# RoboFly.net
KiCad netlist of a schematic drawn in Altium Designer
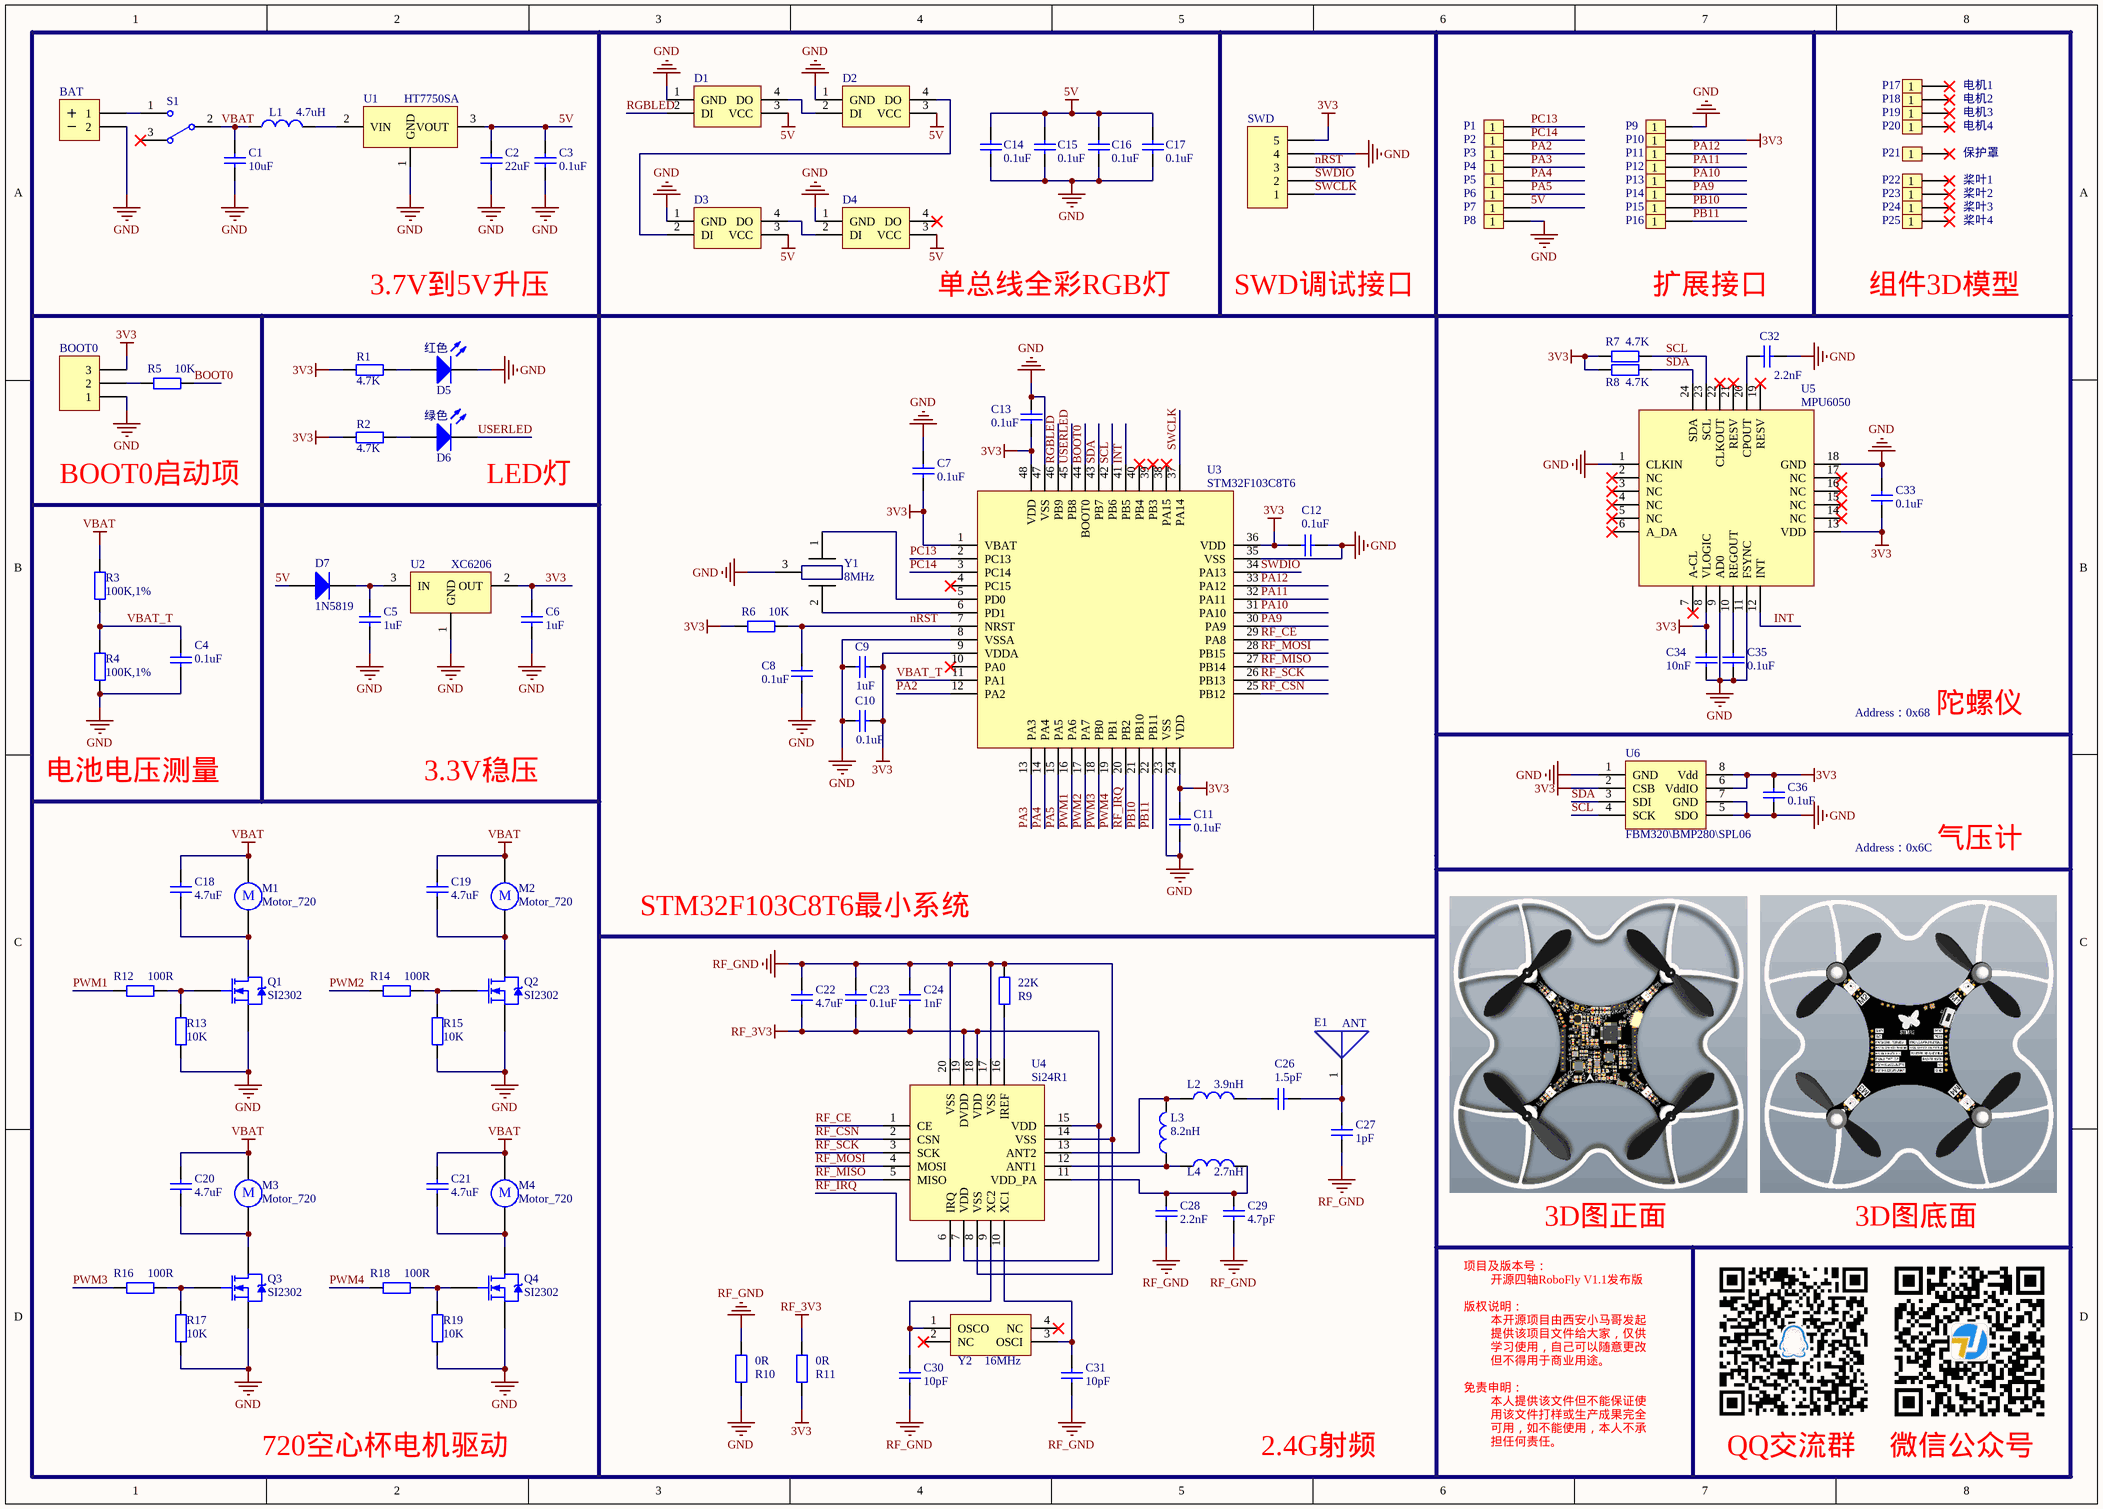
[diagram p0: RoboFly.SchDoc]

(export (version "E")
  (design (tool "Eeschema 10.0.6"))
  (components
    (comp (ref "BAT")
      (value "BAT")
      (footprint "BAT")
      (description "Header, 2-Pin")
      (fields (field (name "PUBLISHER") "mazhongwei"))
      (libsource (lib "RoboFly") (part "BAT"))
    )
    (comp (ref "BOOT0")
      (value "BOOT")
      (footprint "HEADER1X3")
      (description "Header, 3-Pin")
      (fields (field (name "PUBLISHER") "Altium Limited"))
      (libsource (lib "RoboFly") (part "Header 3"))
    )
    (comp (ref "C1")
      (value "10uF")
      (footprint "C_0603")
      (fields (field (name "Comment") "C_0603") (field (name "PUBLISHER") "Altium Limited"))
      (libsource (lib "RoboFly") (part "C_0603"))
    )
    (comp (ref "C2")
      (value "22uF")
      (footprint "C_0603")
      (fields (field (name "Comment") "C_0603") (field (name "PUBLISHER") "Altium Limited"))
      (libsource (lib "RoboFly") (part "C_0603"))
    )
    (comp (ref "C3")
      (value "0.1uF")
      (footprint "C_0603")
      (fields (field (name "Comment") "C_0603") (field (name "PUBLISHER") "Altium Limited"))
      (libsource (lib "RoboFly") (part "C_0603"))
    )
    (comp (ref "C4")
      (value "0.1uF")
      (footprint "C_0603")
      (fields (field (name "Comment") "C_0603") (field (name "PUBLISHER") "Altium Limited"))
      (libsource (lib "RoboFly") (part "C_0603"))
    )
    (comp (ref "C5")
      (value "1uF")
      (footprint "C_0603")
      (fields (field (name "Comment") "C_0603") (field (name "PUBLISHER") "Altium Limited"))
      (libsource (lib "RoboFly") (part "C_0603"))
    )
    (comp (ref "C6")
      (value "1uF")
      (footprint "C_0603")
      (fields (field (name "Comment") "C_0603") (field (name "PUBLISHER") "Altium Limited"))
      (libsource (lib "RoboFly") (part "C_0603"))
    )
    (comp (ref "C7")
      (value "0.1uF")
      (footprint "C_0603")
      (fields (field (name "Comment") "C_0603") (field (name "PUBLISHER") "Altium Limited"))
      (libsource (lib "RoboFly") (part "C_0603"))
    )
    (comp (ref "C8")
      (value "0.1uF")
      (footprint "C_0603")
      (fields (field (name "Comment") "C_0603") (field (name "PUBLISHER") "Altium Limited"))
      (libsource (lib "RoboFly") (part "C_0603"))
    )
    (comp (ref "C9")
      (value "1uF")
      (footprint "C_0603")
      (fields (field (name "Comment") "C_0603") (field (name "PUBLISHER") "Altium Limited"))
      (libsource (lib "RoboFly") (part "C_0603"))
    )
    (comp (ref "C10")
      (value "0.1uF")
      (footprint "C_0603")
      (fields (field (name "Comment") "C_0603") (field (name "PUBLISHER") "Altium Limited"))
      (libsource (lib "RoboFly") (part "C_0603"))
    )
    (comp (ref "C11")
      (value "0.1uF")
      (footprint "C_0603")
      (fields (field (name "Comment") "C_0603") (field (name "PUBLISHER") "Altium Limited"))
      (libsource (lib "RoboFly") (part "C_0603"))
    )
    (comp (ref "C12")
      (value "0.1uF")
      (footprint "C_0603")
      (fields (field (name "Comment") "C_0603") (field (name "PUBLISHER") "Altium Limited"))
      (libsource (lib "RoboFly") (part "C_0603"))
    )
    (comp (ref "C13")
      (value "0.1uF")
      (footprint "C_0603")
      (fields (field (name "Comment") "C_0603") (field (name "PUBLISHER") "Altium Limited"))
      (libsource (lib "RoboFly") (part "C_0603"))
    )
    (comp (ref "C14")
      (value "0.1uF")
      (footprint "C_0603")
      (fields (field (name "Comment") "C_0603") (field (name "PUBLISHER") "Altium Limited"))
      (libsource (lib "RoboFly") (part "C_0603"))
    )
    (comp (ref "C15")
      (value "0.1uF")
      (footprint "C_0603")
      (fields (field (name "Comment") "C_0603") (field (name "PUBLISHER") "Altium Limited"))
      (libsource (lib "RoboFly") (part "C_0603"))
    )
    (comp (ref "C16")
      (value "0.1uF")
      (footprint "C_0603")
      (fields (field (name "Comment") "C_0603") (field (name "PUBLISHER") "Altium Limited"))
      (libsource (lib "RoboFly") (part "C_0603"))
    )
    (comp (ref "C17")
      (value "0.1uF")
      (footprint "C_0603")
      (fields (field (name "Comment") "C_0603") (field (name "PUBLISHER") "Altium Limited"))
      (libsource (lib "RoboFly") (part "C_0603"))
    )
    (comp (ref "C18")
      (value "4.7uF")
      (footprint "C_0603")
      (fields (field (name "Comment") "C_0603") (field (name "PUBLISHER") "Altium Limited"))
      (libsource (lib "RoboFly") (part "C_0603"))
    )
    (comp (ref "C19")
      (value "4.7uF")
      (footprint "C_0603")
      (fields (field (name "Comment") "C_0603") (field (name "PUBLISHER") "Altium Limited"))
      (libsource (lib "RoboFly") (part "C_0603"))
    )
    (comp (ref "C20")
      (value "4.7uF")
      (footprint "C_0603")
      (fields (field (name "Comment") "C_0603") (field (name "PUBLISHER") "Altium Limited"))
      (libsource (lib "RoboFly") (part "C_0603"))
    )
    (comp (ref "C21")
      (value "4.7uF")
      (footprint "C_0603")
      (fields (field (name "Comment") "C_0603") (field (name "PUBLISHER") "Altium Limited"))
      (libsource (lib "RoboFly") (part "C_0603"))
    )
    (comp (ref "C22")
      (value "4.7uF")
      (footprint "C_0603")
      (fields (field (name "Comment") "C_0603") (field (name "PUBLISHER") "Altium Limited"))
      (libsource (lib "RoboFly") (part "C_0603"))
    )
    (comp (ref "C23")
      (value "0.1uF")
      (footprint "C_0603")
      (fields (field (name "Comment") "C_0603") (field (name "PUBLISHER") "Altium Limited"))
      (libsource (lib "RoboFly") (part "C_0603"))
    )
    (comp (ref "C24")
      (value "1nF")
      (footprint "C_0603")
      (fields (field (name "Comment") "C_0603") (field (name "PUBLISHER") "Altium Limited"))
      (libsource (lib "RoboFly") (part "C_0603"))
    )
    (comp (ref "C26")
      (value "1.5pF")
      (footprint "C_0603")
      (fields (field (name "Comment") "C_0603") (field (name "PUBLISHER") "Altium Limited"))
      (libsource (lib "RoboFly") (part "C_0603"))
    )
    (comp (ref "C27")
      (value "1pF")
      (footprint "C_0603")
      (fields (field (name "Comment") "C_0603") (field (name "PUBLISHER") "Altium Limited"))
      (libsource (lib "RoboFly") (part "C_0603"))
    )
    (comp (ref "C28")
      (value "2.2nF")
      (footprint "C_0603")
      (fields (field (name "Comment") "C_0603") (field (name "PUBLISHER") "Altium Limited"))
      (libsource (lib "RoboFly") (part "C_0603"))
    )
    (comp (ref "C29")
      (value "4.7pF")
      (footprint "C_0603")
      (fields (field (name "Comment") "C_0603") (field (name "PUBLISHER") "Altium Limited"))
      (libsource (lib "RoboFly") (part "C_0603"))
    )
    (comp (ref "C30")
      (value "10pF")
      (footprint "C_0603")
      (fields (field (name "Comment") "C_0603") (field (name "PUBLISHER") "Altium Limited"))
      (libsource (lib "RoboFly") (part "C_0603"))
    )
    (comp (ref "C31")
      (value "10pF")
      (footprint "C_0603")
      (fields (field (name "Comment") "C_0603") (field (name "PUBLISHER") "Altium Limited"))
      (libsource (lib "RoboFly") (part "C_0603"))
    )
    (comp (ref "C32")
      (value "2.2nF")
      (footprint "C_0603")
      (fields (field (name "Comment") "C_0603") (field (name "PUBLISHER") "Altium Limited"))
      (libsource (lib "RoboFly") (part "C_0603"))
    )
    (comp (ref "C33")
      (value "0.1uF")
      (footprint "C_0603")
      (fields (field (name "Comment") "C_0603") (field (name "PUBLISHER") "Altium Limited"))
      (libsource (lib "RoboFly") (part "C_0603"))
    )
    (comp (ref "C34")
      (value "10nF")
      (footprint "C_0603")
      (fields (field (name "Comment") "C_0603") (field (name "PUBLISHER") "Altium Limited"))
      (libsource (lib "RoboFly") (part "C_0603"))
    )
    (comp (ref "C35")
      (value "0.1uF")
      (footprint "C_0603")
      (fields (field (name "Comment") "C_0603") (field (name "PUBLISHER") "Altium Limited"))
      (libsource (lib "RoboFly") (part "C_0603"))
    )
    (comp (ref "C36")
      (value "0.1uF")
      (footprint "C_0603")
      (fields (field (name "Comment") "C_0603") (field (name "PUBLISHER") "Altium Limited"))
      (libsource (lib "RoboFly") (part "C_0603"))
    )
    (comp (ref "D1")
      (value "P923D")
      (footprint "RGB_LED_5050")
      (fields (field (name "PUBLISHER") "mazhongwei"))
      (libsource (lib "RoboFly") (part "P923D"))
    )
    (comp (ref "D2")
      (value "P923D")
      (footprint "RGB_LED_5050")
      (fields (field (name "PUBLISHER") "mazhongwei"))
      (libsource (lib "RoboFly") (part "P923D"))
    )
    (comp (ref "D3")
      (value "P923D")
      (footprint "RGB_LED_5050")
      (fields (field (name "PUBLISHER") "mazhongwei"))
      (libsource (lib "RoboFly") (part "P923D"))
    )
    (comp (ref "D4")
      (value "P923D")
      (footprint "RGB_LED_5050")
      (fields (field (name "PUBLISHER") "mazhongwei"))
      (libsource (lib "RoboFly") (part "P923D"))
    )
    (comp (ref "D5")
      (value "红色")
      (footprint "LED-0603")
      (description "发光二极管")
      (fields (field (name "PUBLISHER") "Altium Limited"))
      (libsource (lib "RoboFly") (part "LED 0603"))
    )
    (comp (ref "D6")
      (value "绿色")
      (footprint "LED-0603")
      (description "发光二极管")
      (fields (field (name "PUBLISHER") "Altium Limited"))
      (libsource (lib "RoboFly") (part "LED 0603"))
    )
    (comp (ref "D7")
      (value "1N5819")
      (footprint "SOD-123")
      (description "Default Diode")
      (fields (field (name "PUBLISHER") "mazhongwei"))
      (libsource (lib "RoboFly") (part "Diode"))
    )
    (comp (ref "E1")
      (value "ANT")
      (footprint "ANT")
      (fields (field (name "PUBLISHER") "mazhongwei"))
      (libsource (lib "RoboFly") (part "ANT"))
    )
    (comp (ref "L1")
      (value "4.7uH")
      (footprint "L_1210")
      (description "电感")
      (fields (field (name "Comment") "Inductor") (field (name "PUBLISHER") "Altium Limited"))
      (libsource (lib "RoboFly") (part "Inductor"))
    )
    (comp (ref "L2")
      (value "3.9nH")
      (footprint "L_0603")
      (description "电感")
      (fields (field (name "Comment") "Inductor") (field (name "PUBLISHER") "Altium Limited"))
      (libsource (lib "RoboFly") (part "Inductor_1"))
    )
    (comp (ref "L3")
      (value "8.2nH")
      (footprint "L_0603")
      (description "电感")
      (fields (field (name "Comment") "Inductor") (field (name "PUBLISHER") "Altium Limited"))
      (libsource (lib "RoboFly") (part "Inductor_1"))
    )
    (comp (ref "L4")
      (value "2.7nH")
      (footprint "L_0603")
      (description "电感")
      (fields (field (name "Comment") "Inductor") (field (name "PUBLISHER") "Altium Limited"))
      (libsource (lib "RoboFly") (part "Inductor_1"))
    )
    (comp (ref "M1")
      (value "Motor_720")
      (footprint "MOTOR")
      (description "Motor, General Kind")
      (fields (field (name "PUBLISHER") "mazhongwei"))
      (libsource (lib "RoboFly") (part "Motor_720"))
    )
    (comp (ref "M2")
      (value "Motor_720")
      (footprint "MOTOR")
      (description "Motor, General Kind")
      (fields (field (name "PUBLISHER") "mazhongwei"))
      (libsource (lib "RoboFly") (part "Motor_720"))
    )
    (comp (ref "M3")
      (value "Motor_720")
      (footprint "MOTOR")
      (description "Motor, General Kind")
      (fields (field (name "PUBLISHER") "mazhongwei"))
      (libsource (lib "RoboFly") (part "Motor_720"))
    )
    (comp (ref "M4")
      (value "Motor_720")
      (footprint "MOTOR")
      (description "Motor, General Kind")
      (fields (field (name "PUBLISHER") "mazhongwei"))
      (libsource (lib "RoboFly") (part "Motor_720"))
    )
    (comp (ref "P1")
      (value "Header 1")
      (footprint "HEADER1")
      (fields (field (name "PUBLISHER") "Altium Limited"))
      (libsource (lib "RoboFly") (part "Header 1"))
    )
    (comp (ref "P2")
      (value "Header 1")
      (footprint "HEADER1")
      (fields (field (name "PUBLISHER") "Altium Limited"))
      (libsource (lib "RoboFly") (part "Header 1"))
    )
    (comp (ref "P3")
      (value "Header 1")
      (footprint "HEADER1")
      (fields (field (name "PUBLISHER") "Altium Limited"))
      (libsource (lib "RoboFly") (part "Header 1"))
    )
    (comp (ref "P4")
      (value "Header 1")
      (footprint "HEADER1")
      (fields (field (name "PUBLISHER") "Altium Limited"))
      (libsource (lib "RoboFly") (part "Header 1"))
    )
    (comp (ref "P5")
      (value "Header 1")
      (footprint "HEADER1")
      (fields (field (name "PUBLISHER") "Altium Limited"))
      (libsource (lib "RoboFly") (part "Header 1"))
    )
    (comp (ref "P6")
      (value "Header 1")
      (footprint "HEADER1")
      (fields (field (name "PUBLISHER") "Altium Limited"))
      (libsource (lib "RoboFly") (part "Header 1"))
    )
    (comp (ref "P7")
      (value "Header 1")
      (footprint "HEADER1")
      (fields (field (name "PUBLISHER") "Altium Limited"))
      (libsource (lib "RoboFly") (part "Header 1"))
    )
    (comp (ref "P8")
      (value "Header 1")
      (footprint "HEADER1")
      (fields (field (name "PUBLISHER") "Altium Limited"))
      (libsource (lib "RoboFly") (part "Header 1"))
    )
    (comp (ref "P9")
      (value "Header 1")
      (footprint "HEADER1")
      (fields (field (name "PUBLISHER") "Altium Limited"))
      (libsource (lib "RoboFly") (part "Header 1"))
    )
    (comp (ref "P10")
      (value "Header 1")
      (footprint "HEADER1")
      (fields (field (name "PUBLISHER") "Altium Limited"))
      (libsource (lib "RoboFly") (part "Header 1"))
    )
    (comp (ref "P11")
      (value "Header 1")
      (footprint "HEADER1")
      (fields (field (name "PUBLISHER") "Altium Limited"))
      (libsource (lib "RoboFly") (part "Header 1"))
    )
    (comp (ref "P12")
      (value "Header 1")
      (footprint "HEADER1")
      (fields (field (name "PUBLISHER") "Altium Limited"))
      (libsource (lib "RoboFly") (part "Header 1"))
    )
    (comp (ref "P13")
      (value "Header 1")
      (footprint "HEADER1")
      (fields (field (name "PUBLISHER") "Altium Limited"))
      (libsource (lib "RoboFly") (part "Header 1"))
    )
    (comp (ref "P14")
      (value "Header 1")
      (footprint "HEADER1")
      (fields (field (name "PUBLISHER") "Altium Limited"))
      (libsource (lib "RoboFly") (part "Header 1"))
    )
    (comp (ref "P15")
      (value "Header 1")
      (footprint "HEADER1")
      (fields (field (name "PUBLISHER") "Altium Limited"))
      (libsource (lib "RoboFly") (part "Header 1"))
    )
    (comp (ref "P16")
      (value "Header 1")
      (footprint "HEADER1")
      (fields (field (name "PUBLISHER") "Altium Limited"))
      (libsource (lib "RoboFly") (part "Header 1"))
    )
    (comp (ref "P17")
      (value "Header 1")
      (footprint "720Motor")
      (fields (field (name "PUBLISHER") "Altium Limited"))
      (libsource (lib "RoboFly") (part "Header 1"))
    )
    (comp (ref "P18")
      (value "Header 1")
      (footprint "720Motor")
      (fields (field (name "PUBLISHER") "Altium Limited"))
      (libsource (lib "RoboFly") (part "Header 1"))
    )
    (comp (ref "P19")
      (value "Header 1")
      (footprint "720Motor")
      (fields (field (name "PUBLISHER") "Altium Limited"))
      (libsource (lib "RoboFly") (part "Header 1"))
    )
    (comp (ref "P20")
      (value "Header 1")
      (footprint "720Motor")
      (fields (field (name "PUBLISHER") "Altium Limited"))
      (libsource (lib "RoboFly") (part "Header 1"))
    )
    (comp (ref "P21")
      (value "Header 1")
      (footprint "PROTECT_COVER")
      (fields (field (name "PUBLISHER") "Altium Limited"))
      (libsource (lib "RoboFly") (part "Header 1"))
    )
    (comp (ref "P22")
      (value "Header 1")
      (footprint "BLADEB")
      (fields (field (name "PUBLISHER") "Altium Limited"))
      (libsource (lib "RoboFly") (part "Header 1"))
    )
    (comp (ref "P23")
      (value "Header 1")
      (footprint "BLADEA")
      (fields (field (name "PUBLISHER") "Altium Limited"))
      (libsource (lib "RoboFly") (part "Header 1"))
    )
    (comp (ref "P24")
      (value "Header 1")
      (footprint "BLADEB")
      (fields (field (name "PUBLISHER") "Altium Limited"))
      (libsource (lib "RoboFly") (part "Header 1"))
    )
    (comp (ref "P25")
      (value "Header 1")
      (footprint "BLADEA")
      (fields (field (name "PUBLISHER") "Altium Limited"))
      (libsource (lib "RoboFly") (part "Header 1"))
    )
    (comp (ref "Q1")
      (value "SI2302")
      (footprint "SOT-23(SOT-23-3)")
      (description "N-Channel Power MOSFET")
      (fields (field (name "PUBLISHER") "mazhongwei"))
      (libsource (lib "RoboFly") (part "SI2302"))
    )
    (comp (ref "Q2")
      (value "SI2302")
      (footprint "SOT-23(SOT-23-3)")
      (description "N-Channel Power MOSFET")
      (fields (field (name "PUBLISHER") "mazhongwei"))
      (libsource (lib "RoboFly") (part "SI2302"))
    )
    (comp (ref "Q3")
      (value "SI2302")
      (footprint "SOT-23(SOT-23-3)")
      (description "N-Channel Power MOSFET")
      (fields (field (name "PUBLISHER") "mazhongwei"))
      (libsource (lib "RoboFly") (part "SI2302"))
    )
    (comp (ref "Q4")
      (value "SI2302")
      (footprint "SOT-23(SOT-23-3)")
      (description "N-Channel Power MOSFET")
      (fields (field (name "PUBLISHER") "mazhongwei"))
      (libsource (lib "RoboFly") (part "SI2302"))
    )
    (comp (ref "R1")
      (value "4.7K")
      (footprint "R_0603")
      (fields (field (name "Comment") "R_0603") (field (name "PUBLISHER") "Altium Limited"))
      (libsource (lib "RoboFly") (part "R_0603"))
    )
    (comp (ref "R2")
      (value "4.7K")
      (footprint "R_0603")
      (fields (field (name "Comment") "R_0603") (field (name "PUBLISHER") "Altium Limited"))
      (libsource (lib "RoboFly") (part "R_0603"))
    )
    (comp (ref "R3")
      (value "100K,1%")
      (footprint "R_0603")
      (fields (field (name "Comment") "R_0603") (field (name "PUBLISHER") "Altium Limited"))
      (libsource (lib "") (part "R_0603_1"))
    )
    (comp (ref "R4")
      (value "100K,1%")
      (footprint "R_0603")
      (fields (field (name "Comment") "R_0603") (field (name "PUBLISHER") "Altium Limited"))
      (libsource (lib "") (part "R_0603_1"))
    )
    (comp (ref "R5")
      (value "10K")
      (footprint "R_0603")
      (fields (field (name "Comment") "R_0603") (field (name "PUBLISHER") "Altium Limited"))
      (libsource (lib "RoboFly") (part "R_0603"))
    )
    (comp (ref "R6")
      (value "10K")
      (footprint "R_0603")
      (fields (field (name "Comment") "R_0603") (field (name "PUBLISHER") "Altium Limited"))
      (libsource (lib "") (part "R_0603_2"))
    )
    (comp (ref "R7")
      (value "4.7K")
      (footprint "R_0603")
      (fields (field (name "Comment") "R_0603") (field (name "PUBLISHER") "Altium Limited"))
      (libsource (lib "RoboFly") (part "R_0603"))
    )
    (comp (ref "R8")
      (value "4.7K")
      (footprint "R_0603")
      (fields (field (name "Comment") "R_0603") (field (name "PUBLISHER") "Altium Limited"))
      (libsource (lib "RoboFly") (part "R_0603"))
    )
    (comp (ref "R9")
      (value "22K")
      (footprint "R_0603")
      (fields (field (name "Comment") "R_0603") (field (name "PUBLISHER") "Altium Limited"))
      (libsource (lib "") (part "R_0603_1"))
    )
    (comp (ref "R10")
      (value "0R")
      (footprint "R_0603")
      (fields (field (name "Comment") "R_0603") (field (name "PUBLISHER") "Altium Limited"))
      (libsource (lib "") (part "R_0603_1"))
    )
    (comp (ref "R11")
      (value "0R")
      (footprint "R_0603")
      (fields (field (name "Comment") "R_0603") (field (name "PUBLISHER") "Altium Limited"))
      (libsource (lib "") (part "R_0603_1"))
    )
    (comp (ref "R12")
      (value "100R")
      (footprint "R_0603")
      (fields (field (name "Comment") "R_0603") (field (name "PUBLISHER") "Altium Limited"))
      (libsource (lib "RoboFly") (part "R_0603"))
    )
    (comp (ref "R13")
      (value "10K")
      (footprint "R_0603")
      (fields (field (name "Comment") "R_0603") (field (name "PUBLISHER") "Altium Limited"))
      (libsource (lib "") (part "R_0603_1"))
    )
    (comp (ref "R14")
      (value "100R")
      (footprint "R_0603")
      (fields (field (name "Comment") "R_0603") (field (name "PUBLISHER") "Altium Limited"))
      (libsource (lib "RoboFly") (part "R_0603"))
    )
    (comp (ref "R15")
      (value "10K")
      (footprint "R_0603")
      (fields (field (name "Comment") "R_0603") (field (name "PUBLISHER") "Altium Limited"))
      (libsource (lib "") (part "R_0603_1"))
    )
    (comp (ref "R16")
      (value "100R")
      (footprint "R_0603")
      (fields (field (name "Comment") "R_0603") (field (name "PUBLISHER") "Altium Limited"))
      (libsource (lib "RoboFly") (part "R_0603"))
    )
    (comp (ref "R17")
      (value "10K")
      (footprint "R_0603")
      (fields (field (name "Comment") "R_0603") (field (name "PUBLISHER") "Altium Limited"))
      (libsource (lib "") (part "R_0603_1"))
    )
    (comp (ref "R18")
      (value "100R")
      (footprint "R_0603")
      (fields (field (name "Comment") "R_0603") (field (name "PUBLISHER") "Altium Limited"))
      (libsource (lib "RoboFly") (part "R_0603"))
    )
    (comp (ref "R19")
      (value "10K")
      (footprint "R_0603")
      (fields (field (name "Comment") "R_0603") (field (name "PUBLISHER") "Altium Limited"))
      (libsource (lib "") (part "R_0603_1"))
    )
    (comp (ref "S1")
      (value "SW-SPDT")
      (footprint "SWITCH_PWR")
      (description "SPDT Subminiature Toggle Switch, Right Angle Mounting, Vertical Actuation")
      (fields (field (name "PUBLISHER") "mazhongwei"))
      (libsource (lib "RoboFly") (part "SW-SPDT"))
    )
    (comp (ref "SWD")
      (value "SWD")
      (footprint "SH1_0X5P_WT")
      (description "Header, 5-Pin")
      (fields (field (name "PUBLISHER") "Altium Limited"))
      (libsource (lib "RoboFly") (part "Header 5"))
    )
    (comp (ref "U1")
      (value "HT7750SA")
      (footprint "SOT-23(SOT-23-3)")
      (libsource (lib "RoboFly") (part "HT7750SA"))
    )
    (comp (ref "U2")
      (value "XC6206")
      (footprint "SOT-23(SOT-23-3)")
      (fields (field (name "PUBLISHER") "mazhongwei"))
      (libsource (lib "RoboFly") (part "XC6206"))
    )
    (comp (ref "U3")
      (value "STM32F103C8T6")
      (footprint "LQFP-48_7x7x05P")
      (libsource (lib "RoboFly") (part "STM32F103C8T6"))
    )
    (comp (ref "U4") (value "Si24R1") (footprint "QFN20") (libsource (lib "RoboFly") (part "nRF24L01")))
    (comp (ref "U5")
      (value "MPU6050")
      (footprint "QFN-24_4x4x05P")
      (libsource (lib "RoboFly") (part "MPU6050"))
    )
    (comp (ref "U6")
      (value "FBM32~{0}BMP28~{0}SPL06")
      (footprint "LGA-2_5X2MM")
      (description "气压计")
      (fields (field (name "PUBLISHER") "mazhongwei"))
      (libsource (lib "RoboFly") (part "FBM320"))
    )
    (comp (ref "Y1")
      (value "8MHz")
      (footprint "SMD-cstse800G52-r0")
      (fields (field (name "Comment") "XTAL") (field (name "PUBLISHER") "mazhongwei"))
      (libsource (lib "RoboFly") (part "XTAL_2"))
    )
    (comp (ref "Y2")
      (value "16MHz")
      (footprint "SMD-3225_4P")
      (description "XTAL16M")
      (fields (field (name "Comment") "XTAL"))
      (libsource (lib "RoboFly") (part "XTAL16M"))
    )
  )
  (nets
    (net (code "1") (name "/BOOT0") (class "Default")
      (node (ref "R5") (pin "2") (pinfunction "2_2") (pintype "passive"))
      (node (ref "U3") (pin "44") (pinfunction "BOOT0_44") (pintype "passive"))
    )
    (net (code "2") (name "/INT") (class "Default")
      (node (ref "U3") (pin "41") (pinfunction "PB5_41") (pintype "passive"))
      (node (ref "U5") (pin "12") (pinfunction "INT_12") (pintype "passive"))
    )
    (net (code "3") (name "/PA2") (class "Default")
      (node (ref "P3") (pin "1") (pinfunction "1_1") (pintype "passive"))
      (node (ref "U3") (pin "12") (pinfunction "PA2_12") (pintype "passive"))
    )
    (net (code "4") (name "/PA3") (class "Default")
      (node (ref "P4") (pin "1") (pinfunction "1_1") (pintype "passive"))
      (node (ref "U3") (pin "13") (pinfunction "PA3_13") (pintype "passive"))
    )
    (net (code "5") (name "/PA4") (class "Default")
      (node (ref "P5") (pin "1") (pinfunction "1_1") (pintype "passive"))
      (node (ref "U3") (pin "14") (pinfunction "PA4_14") (pintype "passive"))
    )
    (net (code "6") (name "/PA5") (class "Default")
      (node (ref "P6") (pin "1") (pinfunction "1_1") (pintype "passive"))
      (node (ref "U3") (pin "15") (pinfunction "PA5_15") (pintype "passive"))
    )
    (net (code "7") (name "/PA9") (class "Default")
      (node (ref "P14") (pin "1") (pinfunction "1_1") (pintype "passive"))
      (node (ref "U3") (pin "30") (pinfunction "PA9_30") (pintype "passive"))
    )
    (net (code "8") (name "/PA10") (class "Default")
      (node (ref "P13") (pin "1") (pinfunction "1_1") (pintype "passive"))
      (node (ref "U3") (pin "31") (pinfunction "PA10_31") (pintype "passive"))
    )
    (net (code "9") (name "/PA11") (class "Default")
      (node (ref "P12") (pin "1") (pinfunction "1_1") (pintype "passive"))
      (node (ref "U3") (pin "32") (pinfunction "PA11_32") (pintype "passive"))
    )
    (net (code "10") (name "/PA12") (class "Default")
      (node (ref "P11") (pin "1") (pinfunction "1_1") (pintype "passive"))
      (node (ref "U3") (pin "33") (pinfunction "PA12_33") (pintype "passive"))
    )
    (net (code "11") (name "/PB10") (class "Default")
      (node (ref "P15") (pin "1") (pinfunction "1_1") (pintype "passive"))
      (node (ref "U3") (pin "21") (pinfunction "PB10_21") (pintype "passive"))
    )
    (net (code "12") (name "/PB11") (class "Default")
      (node (ref "P16") (pin "1") (pinfunction "1_1") (pintype "passive"))
      (node (ref "U3") (pin "22") (pinfunction "PB11_22") (pintype "passive"))
    )
    (net (code "13") (name "/PC13") (class "Default")
      (node (ref "P1") (pin "1") (pinfunction "1_1") (pintype "passive"))
      (node (ref "U3") (pin "2") (pinfunction "PC13_2") (pintype "passive"))
    )
    (net (code "14") (name "/PC14") (class "Default")
      (node (ref "P2") (pin "1") (pinfunction "1_1") (pintype "passive"))
      (node (ref "U3") (pin "3") (pinfunction "PC14_3") (pintype "passive"))
    )
    (net (code "15") (name "/PWM1") (class "Default")
      (node (ref "R12") (pin "1") (pinfunction "1_1") (pintype "passive"))
      (node (ref "U3") (pin "16") (pinfunction "PA6_16") (pintype "passive"))
    )
    (net (code "16") (name "/PWM2") (class "Default")
      (node (ref "R14") (pin "1") (pinfunction "1_1") (pintype "passive"))
      (node (ref "U3") (pin "17") (pinfunction "PA7_17") (pintype "passive"))
    )
    (net (code "17") (name "/PWM3") (class "Default")
      (node (ref "R16") (pin "1") (pinfunction "1_1") (pintype "passive"))
      (node (ref "U3") (pin "18") (pinfunction "PB0_18") (pintype "passive"))
    )
    (net (code "18") (name "/PWM4") (class "Default")
      (node (ref "R18") (pin "1") (pinfunction "1_1") (pintype "passive"))
      (node (ref "U3") (pin "19") (pinfunction "PB1_19") (pintype "passive"))
    )
    (net (code "19") (name "/RF_CE") (class "Default")
      (node (ref "U3") (pin "29") (pinfunction "PA8_29") (pintype "passive"))
      (node (ref "U4") (pin "1") (pinfunction "CE_1") (pintype "passive"))
    )
    (net (code "20") (name "/RF_CSN") (class "Default")
      (node (ref "U3") (pin "25") (pinfunction "PB12_25") (pintype "passive"))
      (node (ref "U4") (pin "2") (pinfunction "CSN_2") (pintype "passive"))
    )
    (net (code "21") (name "/RF_IRQ") (class "Default")
      (node (ref "U3") (pin "20") (pinfunction "PB2_20") (pintype "passive"))
      (node (ref "U4") (pin "6") (pinfunction "IRQ_6") (pintype "passive"))
    )
    (net (code "22") (name "/RF_MISO") (class "Default")
      (node (ref "U3") (pin "27") (pinfunction "PB14_27") (pintype "passive"))
      (node (ref "U4") (pin "5") (pinfunction "MISO_5") (pintype "passive"))
    )
    (net (code "23") (name "/RF_MOSI") (class "Default")
      (node (ref "U3") (pin "28") (pinfunction "PB15_28") (pintype "passive"))
      (node (ref "U4") (pin "4") (pinfunction "MOSI_4") (pintype "passive"))
    )
    (net (code "24") (name "/RF_SCK") (class "Default")
      (node (ref "U3") (pin "26") (pinfunction "PB13_26") (pintype "passive"))
      (node (ref "U4") (pin "3") (pinfunction "SCK_3") (pintype "passive"))
    )
    (net (code "25") (name "/RGBLED") (class "Default")
      (node (ref "D1") (pin "2") (pinfunction "DI_2") (pintype "passive"))
      (node (ref "U3") (pin "46") (pinfunction "PB9_46") (pintype "passive"))
    )
    (net (code "26") (name "/SCL") (class "Default")
      (node (ref "R7") (pin "2") (pinfunction "2_2") (pintype "passive"))
      (node (ref "U3") (pin "42") (pinfunction "PB6_42") (pintype "passive"))
      (node (ref "U5") (pin "23") (pinfunction "SCL_23") (pintype "passive"))
      (node (ref "U6") (pin "4") (pinfunction "SCK_4") (pintype "passive"))
    )
    (net (code "27") (name "/SDA") (class "Default")
      (node (ref "R8") (pin "2") (pinfunction "2_2") (pintype "passive"))
      (node (ref "U3") (pin "43") (pinfunction "PB7_43") (pintype "passive"))
      (node (ref "U5") (pin "24") (pinfunction "SDA_24") (pintype "passive"))
      (node (ref "U6") (pin "3") (pinfunction "SDI_3") (pintype "passive"))
    )
    (net (code "28") (name "/SWCLK") (class "Default")
      (node (ref "SWD") (pin "1") (pinfunction "1_1") (pintype "passive"))
      (node (ref "U3") (pin "37") (pinfunction "PA14_37") (pintype "passive"))
    )
    (net (code "29") (name "/SWDIO") (class "Default")
      (node (ref "SWD") (pin "2") (pinfunction "2_2") (pintype "passive"))
      (node (ref "U3") (pin "34") (pinfunction "PA13_34") (pintype "passive"))
    )
    (net (code "30") (name "/USERLED") (class "Default")
      (node (ref "D6") (pin "2") (pinfunction "2_2") (pintype "passive"))
      (node (ref "U3") (pin "45") (pinfunction "PB8_45") (pintype "passive"))
    )
    (net (code "31") (name "/VBAT_T") (class "Default")
      (node (ref "C4") (pin "2") (pinfunction "2_2") (pintype "passive"))
      (node (ref "R3") (pin "1") (pinfunction "1_1") (pintype "passive"))
      (node (ref "R4") (pin "2") (pinfunction "2_2") (pintype "passive"))
      (node (ref "U3") (pin "11") (pinfunction "PA1_11") (pintype "passive"))
    )
    (net (code "32") (name "/nRST") (class "Default")
      (node (ref "C8") (pin "2") (pinfunction "2_2") (pintype "passive"))
      (node (ref "R6") (pin "1") (pinfunction "1_1") (pintype "passive"))
      (node (ref "SWD") (pin "3") (pinfunction "3_3") (pintype "passive"))
      (node (ref "U3") (pin "7") (pinfunction "NRST_7") (pintype "passive"))
    )
    (net (code "33") (name "3V3") (class "Default")
      (node (ref "BOOT0") (pin "3") (pinfunction "3_3") (pintype "passive"))
      (node (ref "C10") (pin "2") (pinfunction "2_2") (pintype "passive"))
      (node (ref "C11") (pin "1") (pinfunction "1_1") (pintype "passive"))
      (node (ref "C12") (pin "2") (pinfunction "2_2") (pintype "passive"))
      (node (ref "C13") (pin "1") (pinfunction "1_1") (pintype "passive"))
      (node (ref "C33") (pin "2") (pinfunction "2_2") (pintype "passive"))
      (node (ref "C34") (pin "2") (pinfunction "2_2") (pintype "passive"))
      (node (ref "C36") (pin "1") (pinfunction "1_1") (pintype "passive"))
      (node (ref "C6") (pin "1") (pinfunction "1_1") (pintype "passive"))
      (node (ref "C7") (pin "2") (pinfunction "2_2") (pintype "passive"))
      (node (ref "C9") (pin "2") (pinfunction "2_2") (pintype "passive"))
      (node (ref "P10") (pin "1") (pinfunction "1_1") (pintype "passive"))
      (node (ref "R1") (pin "1") (pinfunction "1_1") (pintype "passive"))
      (node (ref "R11") (pin "1") (pinfunction "1_1") (pintype "passive"))
      (node (ref "R2") (pin "1") (pinfunction "1_1") (pintype "passive"))
      (node (ref "R6") (pin "2") (pinfunction "2_2") (pintype "passive"))
      (node (ref "R7") (pin "1") (pinfunction "1_1") (pintype "passive"))
      (node (ref "R8") (pin "1") (pinfunction "1_1") (pintype "passive"))
      (node (ref "SWD") (pin "5") (pinfunction "5_5") (pintype "passive"))
      (node (ref "U2") (pin "2") (pinfunction "OUT_2") (pintype "passive"))
      (node (ref "U3") (pin "1") (pinfunction "VBAT_1") (pintype "passive"))
      (node (ref "U3") (pin "24") (pinfunction "VDD_24") (pintype "passive"))
      (node (ref "U3") (pin "36") (pinfunction "VDD_36") (pintype "passive"))
      (node (ref "U3") (pin "48") (pinfunction "VDD_48") (pintype "passive"))
      (node (ref "U3") (pin "9") (pinfunction "VDDA_9") (pintype "passive"))
      (node (ref "U5") (pin "13") (pinfunction "VDD_13") (pintype "passive"))
      (node (ref "U5") (pin "8") (pinfunction "VLOGIC_8") (pintype "passive"))
      (node (ref "U6") (pin "2") (pinfunction "CSB_2") (pintype "passive"))
      (node (ref "U6") (pin "6") (pinfunction "VddIO_6") (pintype "passive"))
      (node (ref "U6") (pin "8") (pinfunction "Vdd_8") (pintype "passive"))
    )
    (net (code "34") (name "5V") (class "Default")
      (node (ref "C14") (pin "2") (pinfunction "2_2") (pintype "passive"))
      (node (ref "C15") (pin "2") (pinfunction "2_2") (pintype "passive"))
      (node (ref "C16") (pin "2") (pinfunction "2_2") (pintype "passive"))
      (node (ref "C17") (pin "2") (pinfunction "2_2") (pintype "passive"))
      (node (ref "C2") (pin "1") (pinfunction "1_1") (pintype "passive"))
      (node (ref "C3") (pin "1") (pinfunction "1_1") (pintype "passive"))
      (node (ref "D1") (pin "3") (pinfunction "VCC_3") (pintype "passive"))
      (node (ref "D2") (pin "3") (pinfunction "VCC_3") (pintype "passive"))
      (node (ref "D3") (pin "3") (pinfunction "VCC_3") (pintype "passive"))
      (node (ref "D4") (pin "3") (pinfunction "VCC_3") (pintype "passive"))
      (node (ref "D7") (pin "1") (pinfunction "A_1") (pintype "passive"))
      (node (ref "P7") (pin "1") (pinfunction "1_1") (pintype "passive"))
      (node (ref "U1") (pin "3") (pinfunction "VOUT_3") (pintype "passive"))
    )
    (net (code "35") (name "GND") (class "Default")
      (node (ref "BAT") (pin "2") (pinfunction "2_2") (pintype "passive"))
      (node (ref "BOOT0") (pin "1") (pinfunction "1_1") (pintype "passive"))
      (node (ref "C1") (pin "2") (pinfunction "2_2") (pintype "passive"))
      (node (ref "C10") (pin "1") (pinfunction "1_1") (pintype "passive"))
      (node (ref "C11") (pin "2") (pinfunction "2_2") (pintype "passive"))
      (node (ref "C12") (pin "1") (pinfunction "1_1") (pintype "passive"))
      (node (ref "C13") (pin "2") (pinfunction "2_2") (pintype "passive"))
      (node (ref "C14") (pin "1") (pinfunction "1_1") (pintype "passive"))
      (node (ref "C15") (pin "1") (pinfunction "1_1") (pintype "passive"))
      (node (ref "C16") (pin "1") (pinfunction "1_1") (pintype "passive"))
      (node (ref "C17") (pin "1") (pinfunction "1_1") (pintype "passive"))
      (node (ref "C2") (pin "2") (pinfunction "2_2") (pintype "passive"))
      (node (ref "C3") (pin "2") (pinfunction "2_2") (pintype "passive"))
      (node (ref "C32") (pin "1") (pinfunction "1_1") (pintype "passive"))
      (node (ref "C33") (pin "1") (pinfunction "1_1") (pintype "passive"))
      (node (ref "C34") (pin "1") (pinfunction "1_1") (pintype "passive"))
      (node (ref "C35") (pin "2") (pinfunction "2_2") (pintype "passive"))
      (node (ref "C36") (pin "2") (pinfunction "2_2") (pintype "passive"))
      (node (ref "C4") (pin "1") (pinfunction "1_1") (pintype "passive"))
      (node (ref "C5") (pin "2") (pinfunction "2_2") (pintype "passive"))
      (node (ref "C6") (pin "2") (pinfunction "2_2") (pintype "passive"))
      (node (ref "C7") (pin "1") (pinfunction "1_1") (pintype "passive"))
      (node (ref "C8") (pin "1") (pinfunction "1_1") (pintype "passive"))
      (node (ref "C9") (pin "1") (pinfunction "1_1") (pintype "passive"))
      (node (ref "D1") (pin "1") (pinfunction "GND_1") (pintype "passive"))
      (node (ref "D2") (pin "1") (pinfunction "GND_1") (pintype "passive"))
      (node (ref "D3") (pin "1") (pinfunction "GND_1") (pintype "passive"))
      (node (ref "D4") (pin "1") (pinfunction "GND_1") (pintype "passive"))
      (node (ref "D5") (pin "2") (pinfunction "2_2") (pintype "passive"))
      (node (ref "P8") (pin "1") (pinfunction "1_1") (pintype "passive"))
      (node (ref "P9") (pin "1") (pinfunction "1_1") (pintype "passive"))
      (node (ref "Q1") (pin "2") (pinfunction "S_2") (pintype "passive"))
      (node (ref "Q2") (pin "2") (pinfunction "S_2") (pintype "passive"))
      (node (ref "Q3") (pin "2") (pinfunction "S_2") (pintype "passive"))
      (node (ref "Q4") (pin "2") (pinfunction "S_2") (pintype "passive"))
      (node (ref "R10") (pin "1") (pinfunction "1_1") (pintype "passive"))
      (node (ref "R13") (pin "1") (pinfunction "1_1") (pintype "passive"))
      (node (ref "R15") (pin "1") (pinfunction "1_1") (pintype "passive"))
      (node (ref "R17") (pin "1") (pinfunction "1_1") (pintype "passive"))
      (node (ref "R19") (pin "1") (pinfunction "1_1") (pintype "passive"))
      (node (ref "R4") (pin "1") (pinfunction "1_1") (pintype "passive"))
      (node (ref "SWD") (pin "4") (pinfunction "4_4") (pintype "passive"))
      (node (ref "U1") (pin "1") (pinfunction "GND_1") (pintype "passive"))
      (node (ref "U2") (pin "1") (pinfunction "GND_1") (pintype "passive"))
      (node (ref "U3") (pin "23") (pinfunction "VSS_23") (pintype "passive"))
      (node (ref "U3") (pin "35") (pinfunction "VSS_35") (pintype "passive"))
      (node (ref "U3") (pin "47") (pinfunction "VSS_47") (pintype "passive"))
      (node (ref "U3") (pin "8") (pinfunction "VSSA_8") (pintype "passive"))
      (node (ref "U5") (pin "1") (pinfunction "CLKIN_1") (pintype "passive"))
      (node (ref "U5") (pin "11") (pinfunction "FSYNC_11") (pintype "passive"))
      (node (ref "U5") (pin "18") (pinfunction "GND_18") (pintype "passive"))
      (node (ref "U5") (pin "9") (pinfunction "AD0_9") (pintype "passive"))
      (node (ref "U6") (pin "1") (pinfunction "GND_1") (pintype "passive"))
      (node (ref "U6") (pin "5") (pinfunction "SDO_5") (pintype "passive"))
      (node (ref "U6") (pin "7") (pinfunction "GND_7") (pintype "passive"))
      (node (ref "Y1") (pin "3") (pinfunction "3_3") (pintype "passive"))
    )
    (net (code "36") (name "Net-(BAT-Pad1)") (class "Default")
      (node (ref "BAT") (pin "1") (pinfunction "1_1") (pintype "passive"))
      (node (ref "S1") (pin "1") (pinfunction "1_1") (pintype "passive"))
    )
    (net (code "37") (name "Net-(BOOT0-Pad2)") (class "Default")
      (node (ref "BOOT0") (pin "2") (pinfunction "2_2") (pintype "passive"))
      (node (ref "R5") (pin "1") (pinfunction "1_1") (pintype "passive"))
    )
    (net (code "38") (name "Net-(C26-Pad1)") (class "Default")
      (node (ref "C26") (pin "1") (pinfunction "1_1") (pintype "passive"))
      (node (ref "L2") (pin "2") (pinfunction "2_2") (pintype "passive"))
    )
    (net (code "39") (name "Net-(C26-Pad2)") (class "Default")
      (node (ref "C26") (pin "2") (pinfunction "2_2") (pintype "passive"))
      (node (ref "C27") (pin "2") (pinfunction "2_2") (pintype "passive"))
      (node (ref "E1") (pin "1") (pinfunction "1_1") (pintype "passive"))
    )
    (net (code "40") (name "Net-(D1-DO)") (class "Default")
      (node (ref "D1") (pin "4") (pinfunction "DO_4") (pintype "passive"))
      (node (ref "D2") (pin "2") (pinfunction "DI_2") (pintype "passive"))
    )
    (net (code "41") (name "Net-(D2-DO)") (class "Default")
      (node (ref "D2") (pin "4") (pinfunction "DO_4") (pintype "passive"))
      (node (ref "D3") (pin "2") (pinfunction "DI_2") (pintype "passive"))
    )
    (net (code "42") (name "Net-(D3-DO)") (class "Default")
      (node (ref "D3") (pin "4") (pinfunction "DO_4") (pintype "passive"))
      (node (ref "D4") (pin "2") (pinfunction "DI_2") (pintype "passive"))
    )
    (net (code "43") (name "Net-(D5-Pad1)") (class "Default")
      (node (ref "D5") (pin "1") (pinfunction "1_1") (pintype "passive"))
      (node (ref "R1") (pin "2") (pinfunction "2_2") (pintype "passive"))
    )
    (net (code "44") (name "Net-(D6-Pad1)") (class "Default")
      (node (ref "D6") (pin "1") (pinfunction "1_1") (pintype "passive"))
      (node (ref "R2") (pin "2") (pinfunction "2_2") (pintype "passive"))
    )
    (net (code "45") (name "Net-(D7-K)") (class "Default")
      (node (ref "C5") (pin "1") (pinfunction "1_1") (pintype "passive"))
      (node (ref "D7") (pin "2") (pinfunction "K_2") (pintype "passive"))
      (node (ref "U2") (pin "3") (pinfunction "IN_3") (pintype "passive"))
    )
    (net (code "46") (name "Net-(Q1-D)") (class "Default")
      (node (ref "C18") (pin "1") (pinfunction "1_1") (pintype "passive"))
      (node (ref "M1") (pin "2") (pinfunction "2_2") (pintype "passive"))
      (node (ref "Q1") (pin "3") (pinfunction "D_3") (pintype "passive"))
    )
    (net (code "47") (name "Net-(Q1-G)") (class "Default")
      (node (ref "Q1") (pin "1") (pinfunction "G_1") (pintype "passive"))
      (node (ref "R12") (pin "2") (pinfunction "2_2") (pintype "passive"))
      (node (ref "R13") (pin "2") (pinfunction "2_2") (pintype "passive"))
    )
    (net (code "48") (name "Net-(Q2-D)") (class "Default")
      (node (ref "C19") (pin "1") (pinfunction "1_1") (pintype "passive"))
      (node (ref "M2") (pin "2") (pinfunction "2_2") (pintype "passive"))
      (node (ref "Q2") (pin "3") (pinfunction "D_3") (pintype "passive"))
    )
    (net (code "49") (name "Net-(Q2-G)") (class "Default")
      (node (ref "Q2") (pin "1") (pinfunction "G_1") (pintype "passive"))
      (node (ref "R14") (pin "2") (pinfunction "2_2") (pintype "passive"))
      (node (ref "R15") (pin "2") (pinfunction "2_2") (pintype "passive"))
    )
    (net (code "50") (name "Net-(Q3-D)") (class "Default")
      (node (ref "C20") (pin "1") (pinfunction "1_1") (pintype "passive"))
      (node (ref "M3") (pin "2") (pinfunction "2_2") (pintype "passive"))
      (node (ref "Q3") (pin "3") (pinfunction "D_3") (pintype "passive"))
    )
    (net (code "51") (name "Net-(Q3-G)") (class "Default")
      (node (ref "Q3") (pin "1") (pinfunction "G_1") (pintype "passive"))
      (node (ref "R16") (pin "2") (pinfunction "2_2") (pintype "passive"))
      (node (ref "R17") (pin "2") (pinfunction "2_2") (pintype "passive"))
    )
    (net (code "52") (name "Net-(Q4-D)") (class "Default")
      (node (ref "C21") (pin "1") (pinfunction "1_1") (pintype "passive"))
      (node (ref "M4") (pin "2") (pinfunction "2_2") (pintype "passive"))
      (node (ref "Q4") (pin "3") (pinfunction "D_3") (pintype "passive"))
    )
    (net (code "53") (name "Net-(Q4-G)") (class "Default")
      (node (ref "Q4") (pin "1") (pinfunction "G_1") (pintype "passive"))
      (node (ref "R18") (pin "2") (pinfunction "2_2") (pintype "passive"))
      (node (ref "R19") (pin "2") (pinfunction "2_2") (pintype "passive"))
    )
    (net (code "54") (name "Net-(U1-VIN)") (class "Default")
      (node (ref "L1") (pin "2") (pinfunction "2_2") (pintype "passive"))
      (node (ref "U1") (pin "2") (pinfunction "VIN_2") (pintype "passive"))
    )
    (net (code "55") (name "Net-(U3-PD0)") (class "Default")
      (node (ref "U3") (pin "5") (pinfunction "PD0_5") (pintype "passive"))
      (node (ref "Y1") (pin "1") (pinfunction "1_1") (pintype "passive"))
    )
    (net (code "56") (name "Net-(U3-PD1)") (class "Default")
      (node (ref "U3") (pin "6") (pinfunction "PD1_6") (pintype "passive"))
      (node (ref "Y1") (pin "2") (pinfunction "2_2") (pintype "passive"))
    )
    (net (code "57") (name "Net-(U4-ANT1)") (class "Default")
      (node (ref "L3") (pin "1") (pinfunction "1_1") (pintype "passive"))
      (node (ref "L4") (pin "1") (pinfunction "1_1") (pintype "passive"))
      (node (ref "U4") (pin "12") (pinfunction "ANT1_12") (pintype "passive"))
    )
    (net (code "58") (name "Net-(U4-ANT2)") (class "Default")
      (node (ref "L2") (pin "1") (pinfunction "1_1") (pintype "passive"))
      (node (ref "L3") (pin "2") (pinfunction "2_2") (pintype "passive"))
      (node (ref "U4") (pin "13") (pinfunction "ANT2_13") (pintype "passive"))
    )
    (net (code "59") (name "Net-(U4-IREF)") (class "Default")
      (node (ref "R9") (pin "1") (pinfunction "1_1") (pintype "passive"))
      (node (ref "U4") (pin "16") (pinfunction "IREF_16") (pintype "passive"))
    )
    (net (code "60") (name "Net-(U4-VDD_PA)") (class "Default")
      (node (ref "C28") (pin "2") (pinfunction "2_2") (pintype "passive"))
      (node (ref "C29") (pin "2") (pinfunction "2_2") (pintype "passive"))
      (node (ref "L4") (pin "2") (pinfunction "2_2") (pintype "passive"))
      (node (ref "U4") (pin "11") (pinfunction "VDD_PA_11") (pintype "passive"))
    )
    (net (code "61") (name "Net-(U4-XC1)") (class "Default")
      (node (ref "C31") (pin "2") (pinfunction "2_2") (pintype "passive"))
      (node (ref "U4") (pin "10") (pinfunction "XC1_10") (pintype "passive"))
      (node (ref "Y2") (pin "3") (pinfunction "OSCI_3") (pintype "passive"))
    )
    (net (code "62") (name "Net-(U4-XC2)") (class "Default")
      (node (ref "C30") (pin "2") (pinfunction "2_2") (pintype "passive"))
      (node (ref "U4") (pin "9") (pinfunction "XC2_9") (pintype "passive"))
      (node (ref "Y2") (pin "1") (pinfunction "OSCO_1") (pintype "passive"))
    )
    (net (code "63") (name "Net-(U5-CPOUT)") (class "Default")
      (node (ref "C32") (pin "2") (pinfunction "2_2") (pintype "passive"))
      (node (ref "U5") (pin "20") (pinfunction "CPOUT_20") (pintype "passive"))
    )
    (net (code "64") (name "Net-(U5-REGOUT)") (class "Default")
      (node (ref "C35") (pin "1") (pinfunction "1_1") (pintype "passive"))
      (node (ref "U5") (pin "10") (pinfunction "REGOUT_10") (pintype "passive"))
    )
    (net (code "65") (name "RF_3V3") (class "Default")
      (node (ref "C22") (pin "1") (pinfunction "1_1") (pintype "passive"))
      (node (ref "C23") (pin "1") (pinfunction "1_1") (pintype "passive"))
      (node (ref "C24") (pin "1") (pinfunction "1_1") (pintype "passive"))
      (node (ref "R11") (pin "2") (pinfunction "2_2") (pintype "passive"))
      (node (ref "U4") (pin "15") (pinfunction "VDD_15") (pintype "passive"))
      (node (ref "U4") (pin "18") (pinfunction "VDD_18") (pintype "passive"))
      (node (ref "U4") (pin "19") (pinfunction "DVDD_19") (pintype "passive"))
      (node (ref "U4") (pin "7") (pinfunction "VDD_7") (pintype "passive"))
    )
    (net (code "66") (name "RF_GND") (class "Default")
      (node (ref "C22") (pin "2") (pinfunction "2_2") (pintype "passive"))
      (node (ref "C23") (pin "2") (pinfunction "2_2") (pintype "passive"))
      (node (ref "C24") (pin "2") (pinfunction "2_2") (pintype "passive"))
      (node (ref "C27") (pin "1") (pinfunction "1_1") (pintype "passive"))
      (node (ref "C28") (pin "1") (pinfunction "1_1") (pintype "passive"))
      (node (ref "C29") (pin "1") (pinfunction "1_1") (pintype "passive"))
      (node (ref "C30") (pin "1") (pinfunction "1_1") (pintype "passive"))
      (node (ref "C31") (pin "1") (pinfunction "1_1") (pintype "passive"))
      (node (ref "R10") (pin "2") (pinfunction "2_2") (pintype "passive"))
      (node (ref "R9") (pin "2") (pinfunction "2_2") (pintype "passive"))
      (node (ref "U4") (pin "14") (pinfunction "VSS_14") (pintype "passive"))
      (node (ref "U4") (pin "17") (pinfunction "VSS_17") (pintype "passive"))
      (node (ref "U4") (pin "20") (pinfunction "VSS_20") (pintype "passive"))
      (node (ref "U4") (pin "8") (pinfunction "VSS_8") (pintype "passive"))
    )
    (net (code "67") (name "VBAT") (class "Default")
      (node (ref "C1") (pin "1") (pinfunction "1_1") (pintype "passive"))
      (node (ref "C18") (pin "2") (pinfunction "2_2") (pintype "passive"))
      (node (ref "C19") (pin "2") (pinfunction "2_2") (pintype "passive"))
      (node (ref "C20") (pin "2") (pinfunction "2_2") (pintype "passive"))
      (node (ref "C21") (pin "2") (pinfunction "2_2") (pintype "passive"))
      (node (ref "L1") (pin "1") (pinfunction "1_1") (pintype "passive"))
      (node (ref "M1") (pin "1") (pinfunction "1_1") (pintype "passive"))
      (node (ref "M2") (pin "1") (pinfunction "1_1") (pintype "passive"))
      (node (ref "M3") (pin "1") (pinfunction "1_1") (pintype "passive"))
      (node (ref "M4") (pin "1") (pinfunction "1_1") (pintype "passive"))
      (node (ref "R3") (pin "2") (pinfunction "2_2") (pintype "passive"))
      (node (ref "S1") (pin "2") (pinfunction "2_2") (pintype "passive"))
    )
    (net (code "68") (name "unconnected-(D4-DO-Pad4)") (class "Default")
      (node (ref "D4") (pin "4") (pinfunction "DO_4") (pintype "passive+no_connect"))
    )
    (net (code "69") (name "unconnected-(P17-Pad1)") (class "Default")
      (node (ref "P17") (pin "1") (pinfunction "1_1") (pintype "passive+no_connect"))
    )
    (net (code "70") (name "unconnected-(P18-Pad1)") (class "Default")
      (node (ref "P18") (pin "1") (pinfunction "1_1") (pintype "passive+no_connect"))
    )
    (net (code "71") (name "unconnected-(P19-Pad1)") (class "Default")
      (node (ref "P19") (pin "1") (pinfunction "1_1") (pintype "passive+no_connect"))
    )
    (net (code "72") (name "unconnected-(P20-Pad1)") (class "Default")
      (node (ref "P20") (pin "1") (pinfunction "1_1") (pintype "passive+no_connect"))
    )
    (net (code "73") (name "unconnected-(P21-Pad1)") (class "Default")
      (node (ref "P21") (pin "1") (pinfunction "1_1") (pintype "passive+no_connect"))
    )
    (net (code "74") (name "unconnected-(P22-Pad1)") (class "Default")
      (node (ref "P22") (pin "1") (pinfunction "1_1") (pintype "passive+no_connect"))
    )
    (net (code "75") (name "unconnected-(P23-Pad1)") (class "Default")
      (node (ref "P23") (pin "1") (pinfunction "1_1") (pintype "passive+no_connect"))
    )
    (net (code "76") (name "unconnected-(P24-Pad1)") (class "Default")
      (node (ref "P24") (pin "1") (pinfunction "1_1") (pintype "passive+no_connect"))
    )
    (net (code "77") (name "unconnected-(P25-Pad1)") (class "Default")
      (node (ref "P25") (pin "1") (pinfunction "1_1") (pintype "passive+no_connect"))
    )
    (net (code "78") (name "unconnected-(S1-Pad3)") (class "Default")
      (node (ref "S1") (pin "3") (pinfunction "3_3") (pintype "passive+no_connect"))
    )
    (net (code "79") (name "unconnected-(U3-PA0-Pad10)") (class "Default")
      (node (ref "U3") (pin "10") (pinfunction "PA0_10") (pintype "passive+no_connect"))
    )
    (net (code "80") (name "unconnected-(U3-PA15-Pad38)") (class "Default")
      (node (ref "U3") (pin "38") (pinfunction "PA15_38") (pintype "passive+no_connect"))
    )
    (net (code "81") (name "unconnected-(U3-PB3-Pad39)") (class "Default")
      (node (ref "U3") (pin "39") (pinfunction "PB3_39") (pintype "passive+no_connect"))
    )
    (net (code "82") (name "unconnected-(U3-PB4-Pad40)") (class "Default")
      (node (ref "U3") (pin "40") (pinfunction "PB4_40") (pintype "passive+no_connect"))
    )
    (net (code "83") (name "unconnected-(U3-PC15-Pad4)") (class "Default")
      (node (ref "U3") (pin "4") (pinfunction "PC15_4") (pintype "passive+no_connect"))
    )
    (net (code "84") (name "unconnected-(U5-A-CL-Pad7)") (class "Default")
      (node (ref "U5") (pin "7") (pinfunction "A-CL_7") (pintype "passive+no_connect"))
    )
    (net (code "85") (name "unconnected-(U5-A_DA-Pad6)") (class "Default")
      (node (ref "U5") (pin "6") (pinfunction "A_DA_6") (pintype "passive+no_connect"))
    )
    (net (code "86") (name "unconnected-(U5-CLKOUT-Pad22)") (class "Default")
      (node (ref "U5") (pin "22") (pinfunction "CLKOUT_22") (pintype "passive+no_connect"))
    )
    (net (code "87") (name "unconnected-(U5-NC-Pad2)") (class "Default")
      (node (ref "U5") (pin "2") (pinfunction "NC_2") (pintype "passive+no_connect"))
    )
    (net (code "88") (name "unconnected-(U5-NC-Pad3)") (class "Default")
      (node (ref "U5") (pin "3") (pinfunction "NC_3") (pintype "passive+no_connect"))
    )
    (net (code "89") (name "unconnected-(U5-NC-Pad4)") (class "Default")
      (node (ref "U5") (pin "4") (pinfunction "NC_4") (pintype "passive+no_connect"))
    )
    (net (code "90") (name "unconnected-(U5-NC-Pad5)") (class "Default")
      (node (ref "U5") (pin "5") (pinfunction "NC_5") (pintype "passive+no_connect"))
    )
    (net (code "91") (name "unconnected-(U5-NC-Pad14)") (class "Default")
      (node (ref "U5") (pin "14") (pinfunction "NC_14") (pintype "passive+no_connect"))
    )
    (net (code "92") (name "unconnected-(U5-NC-Pad15)") (class "Default")
      (node (ref "U5") (pin "15") (pinfunction "NC_15") (pintype "passive+no_connect"))
    )
    (net (code "93") (name "unconnected-(U5-NC-Pad16)") (class "Default")
      (node (ref "U5") (pin "16") (pinfunction "NC_16") (pintype "passive+no_connect"))
    )
    (net (code "94") (name "unconnected-(U5-NC-Pad17)") (class "Default")
      (node (ref "U5") (pin "17") (pinfunction "NC_17") (pintype "passive+no_connect"))
    )
    (net (code "95") (name "unconnected-(U5-RESV-Pad19)") (class "Default")
      (node (ref "U5") (pin "19") (pinfunction "RESV_19") (pintype "passive+no_connect"))
    )
    (net (code "96") (name "unconnected-(U5-RESV-Pad21)") (class "Default")
      (node (ref "U5") (pin "21") (pinfunction "RESV_21") (pintype "passive+no_connect"))
    )
    (net (code "97") (name "unconnected-(Y2-NC-Pad2)") (class "Default")
      (node (ref "Y2") (pin "2") (pinfunction "NC_2") (pintype "passive+no_connect"))
    )
    (net (code "98") (name "unconnected-(Y2-NC-Pad4)") (class "Default")
      (node (ref "Y2") (pin "4") (pinfunction "NC_4") (pintype "passive+no_connect"))
    )
  )
)
